# power2.net
KiCad netlist of a schematic drawn in Altium Designer
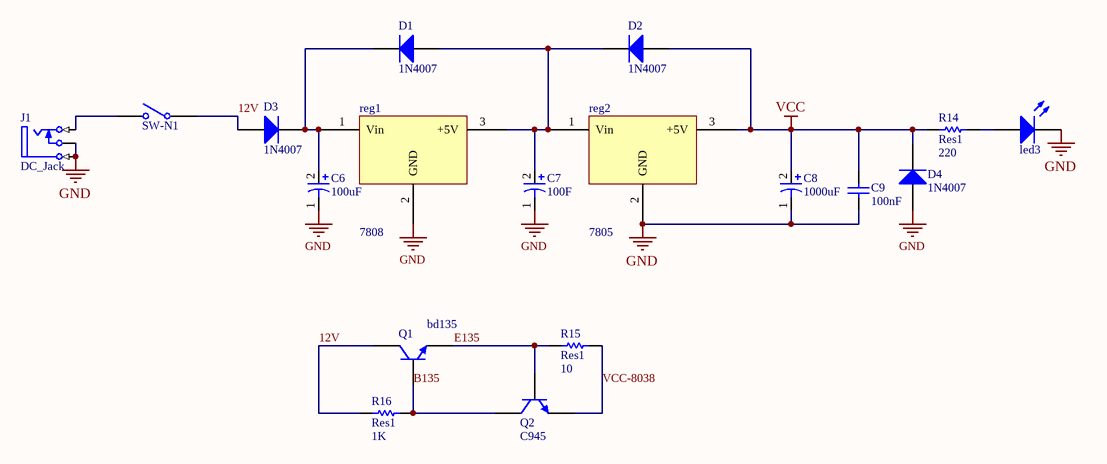
[diagram p0: power2.SchDoc]

(export (version "E")
  (design (tool "Eeschema 10.0.6"))
  (components
    (comp (ref "C6")
      (value "100uF")
      (footprint "Cap-Polar-5.5mm")
      (description "Polarized Capacitor (Axial)")
      (fields (field (name "Comment") "Cap-Polar") (field (name "PUBLISHER") "Altium Limited"))
      (libsource (lib "Mine-Discreet") (part "Cap-Polar"))
    )
    (comp (ref "C7")
      (value "100F")
      (footprint "Cap-Polar-5.5mm")
      (description "Polarized Capacitor (Axial)")
      (fields (field (name "Comment") "Cap-Polar") (field (name "PUBLISHER") "Altium Limited"))
      (libsource (lib "Mine-Discreet") (part "Cap-Polar"))
    )
    (comp (ref "C8")
      (value "1000uF")
      (footprint "Cap-Polar-10.5mm")
      (description "Polarized Capacitor (Axial)")
      (fields (field (name "Comment") "Cap-Polar") (field (name "PUBLISHER") "Altium Limited"))
      (libsource (lib "Mine-Discreet") (part "Cap-Polar"))
    )
    (comp (ref "C9")
      (value "100nF")
      (footprint "My_cap100n")
      (description "Capacitor")
      (fields (field (name "Comment") "Cap-NF") (field (name "PUBLISHER") "Altium Limited"))
      (libsource (lib "Mine-Discreet") (part "Cap-NF"))
    )
    (comp (ref "D1")
      (value "1N4007")
      (footprint "DO-41")
      (description "1 Amp Diode")
      (libsource (lib "Altium library (www.AVRelec.com)") (part "1N4007"))
    )
    (comp (ref "D2")
      (value "1N4007")
      (footprint "DO-41")
      (description "1 Amp Diode")
      (libsource (lib "Altium library (www.AVRelec.com)") (part "1N4007"))
    )
    (comp (ref "D3")
      (value "1N4007")
      (footprint "DO-41")
      (description "1 Amp Diode")
      (libsource (lib "Altium library (www.AVRelec.com)") (part "1N4007"))
    )
    (comp (ref "D4")
      (value "1N4007")
      (footprint "DO-41")
      (description "1 Amp Diode")
      (libsource (lib "Altium library (www.AVRelec.com)") (part "1N4007"))
    )
    (comp (ref "J1")
      (value "DC_Jack")
      (footprint "Power Jack")
      (fields (field (name "PUBLISHER") "Altium Limited"))
      (libsource (lib "Altium library (www.AVRelec.com)") (part "DC_Jack"))
    )
    (comp (ref "led3")
      (value "LED 5mm")
      (footprint "Mine-Discreet:LED-5mm")
      (description "Typical LED")
      (fields (field (name "DESIGNER") "Seyed Mohsen Ghasemian") (field (name "PUBLISHER") "www.picpars.com"))
      (libsource (lib "PicPars.com_usefully_Library") (part "LED 5mm"))
    )
    (comp (ref "Q1")
      (value "bd135")
      (footprint "SOT-32")
      (description "NPN Transistor")
      (fields (field (name "DESIGNER") "Saeid Jorablo"))
      (libsource (lib "My Library") (part "C945"))
    )
    (comp (ref "Q2")
      (value "C945")
      (footprint "C945")
      (description "NPN Transistor")
      (fields (field (name "DESIGNER") "Saeid Jorablo"))
      (libsource (lib "My Library") (part "C945"))
    )
    (comp (ref "R14")
      (value "Res1")
      (footprint "AXIAL-0.3")
      (description "Resistor")
      (fields (field (name "ALTIUM_VALUE") "220") (field (name "PUBLISHER") "Altium Limited"))
      (libsource (lib "Miscellaneous Devices") (part "Res1"))
    )
    (comp (ref "R15")
      (value "Res1")
      (footprint "AXIAL-0.3")
      (description "Resistor")
      (fields (field (name "ALTIUM_VALUE") "10") (field (name "PUBLISHER") "Altium Limited"))
      (libsource (lib "Miscellaneous Devices") (part "Res1"))
    )
    (comp (ref "R16")
      (value "Res1")
      (footprint "AXIAL-0.3")
      (description "Resistor")
      (fields (field (name "ALTIUM_VALUE") "1K") (field (name "PUBLISHER") "Altium Limited"))
      (libsource (lib "Miscellaneous Devices") (part "Res1"))
    )
    (comp (ref "reg1")
      (value "7808")
      (footprint "REG-7805-smd")
      (description "Regulator")
      (libsource (lib "Altium library (www.AVRelec.com)") (part "7805"))
    )
    (comp (ref "reg2")
      (value "7805")
      (footprint "REG-7805-smd")
      (description "Regulator")
      (libsource (lib "Altium library (www.AVRelec.com)") (part "7805"))
    )
    (comp (ref "SW-N1")
      (value "Switch-1 way")
      (footprint "rocker - switch")
      (libsource (lib "Mine-Discreet") (part "Switch-1 way"))
    )
  )
  (nets
    (net (code "1") (name "/12V") (class "Default")
      (node (ref "D3") (pin "A") (pinfunction "A_A") (pintype "passive"))
      (node (ref "Q1") (pin "2") (pinfunction "C_2") (pintype "passive"))
      (node (ref "R16") (pin "1") (pinfunction "1_1") (pintype "passive"))
      (node (ref "SW-N1") (pin "1") (pinfunction "COMMON_1") (pintype "passive"))
    )
    (net (code "2") (name "/B135") (class "Default")
      (node (ref "Q1") (pin "3") (pinfunction "B_3") (pintype "passive"))
      (node (ref "Q2") (pin "2") (pinfunction "C_2") (pintype "passive"))
      (node (ref "R16") (pin "2") (pinfunction "2_2") (pintype "passive"))
    )
    (net (code "3") (name "/E135") (class "Default")
      (node (ref "Q1") (pin "1") (pinfunction "E_1") (pintype "passive"))
      (node (ref "Q2") (pin "3") (pinfunction "B_3") (pintype "passive"))
      (node (ref "R15") (pin "1") (pinfunction "1_1") (pintype "passive"))
    )
    (net (code "4") (name "/VCC-8038") (class "Default")
      (node (ref "Q2") (pin "1") (pinfunction "E_1") (pintype "passive"))
      (node (ref "R15") (pin "2") (pinfunction "2_2") (pintype "passive"))
    )
    (net (code "5") (name "GND") (class "Default")
      (node (ref "C6") (pin "1") (pinfunction "1_1") (pintype "passive"))
      (node (ref "C7") (pin "1") (pinfunction "1_1") (pintype "passive"))
      (node (ref "C8") (pin "1") (pinfunction "1_1") (pintype "passive"))
      (node (ref "C9") (pin "2") (pinfunction "2_2") (pintype "passive"))
      (node (ref "D4") (pin "A") (pinfunction "A_A") (pintype "passive"))
      (node (ref "J1") (pin "2") (pinfunction "TN_2") (pintype "passive"))
      (node (ref "J1") (pin "3") (pinfunction "S_3") (pintype "input"))
      (node (ref "led3") (pin "2") (pinfunction "K_2") (pintype "passive"))
      (node (ref "reg1") (pin "2") (pinfunction "GND_2") (pintype "power_in"))
      (node (ref "reg2") (pin "2") (pinfunction "GND_2") (pintype "power_in"))
    )
    (net (code "6") (name "Net-(J1-T)") (class "Default")
      (node (ref "J1") (pin "1") (pinfunction "T_1") (pintype "input"))
      (node (ref "SW-N1") (pin "2") (pinfunction "NO_2") (pintype "passive"))
    )
    (net (code "7") (name "Net-(led3-A)") (class "Default")
      (node (ref "R14") (pin "2") (pinfunction "2_2") (pintype "passive"))
      (node (ref "led3") (pin "1") (pinfunction "A_1") (pintype "passive"))
    )
    (net (code "8") (name "Net-(reg1-+5V)") (class "Default")
      (node (ref "C7") (pin "2") (pinfunction "2_2") (pintype "passive"))
      (node (ref "D1") (pin "A") (pinfunction "A_A") (pintype "passive"))
      (node (ref "D2") (pin "K") (pinfunction "K_K") (pintype "passive"))
      (node (ref "reg1") (pin "3") (pinfunction "+5V_3") (pintype "power_in"))
      (node (ref "reg2") (pin "1") (pinfunction "Vin_1") (pintype "power_in"))
    )
    (net (code "9") (name "Net-(reg1-Vin)") (class "Default")
      (node (ref "C6") (pin "2") (pinfunction "2_2") (pintype "passive"))
      (node (ref "D1") (pin "K") (pinfunction "K_K") (pintype "passive"))
      (node (ref "D3") (pin "K") (pinfunction "K_K") (pintype "passive"))
      (node (ref "reg1") (pin "1") (pinfunction "Vin_1") (pintype "power_in"))
    )
    (net (code "10") (name "VCC") (class "Default")
      (node (ref "C8") (pin "2") (pinfunction "2_2") (pintype "passive"))
      (node (ref "C9") (pin "1") (pinfunction "1_1") (pintype "passive"))
      (node (ref "D2") (pin "A") (pinfunction "A_A") (pintype "passive"))
      (node (ref "D4") (pin "K") (pinfunction "K_K") (pintype "passive"))
      (node (ref "R14") (pin "1") (pinfunction "1_1") (pintype "passive"))
      (node (ref "reg2") (pin "3") (pinfunction "+5V_3") (pintype "power_in"))
    )
  )
)
